# SCH_M5_GreenHat_Coil_Driver_2021-08-27.net
KiCad netlist of a schematic drawn in EasyEDA
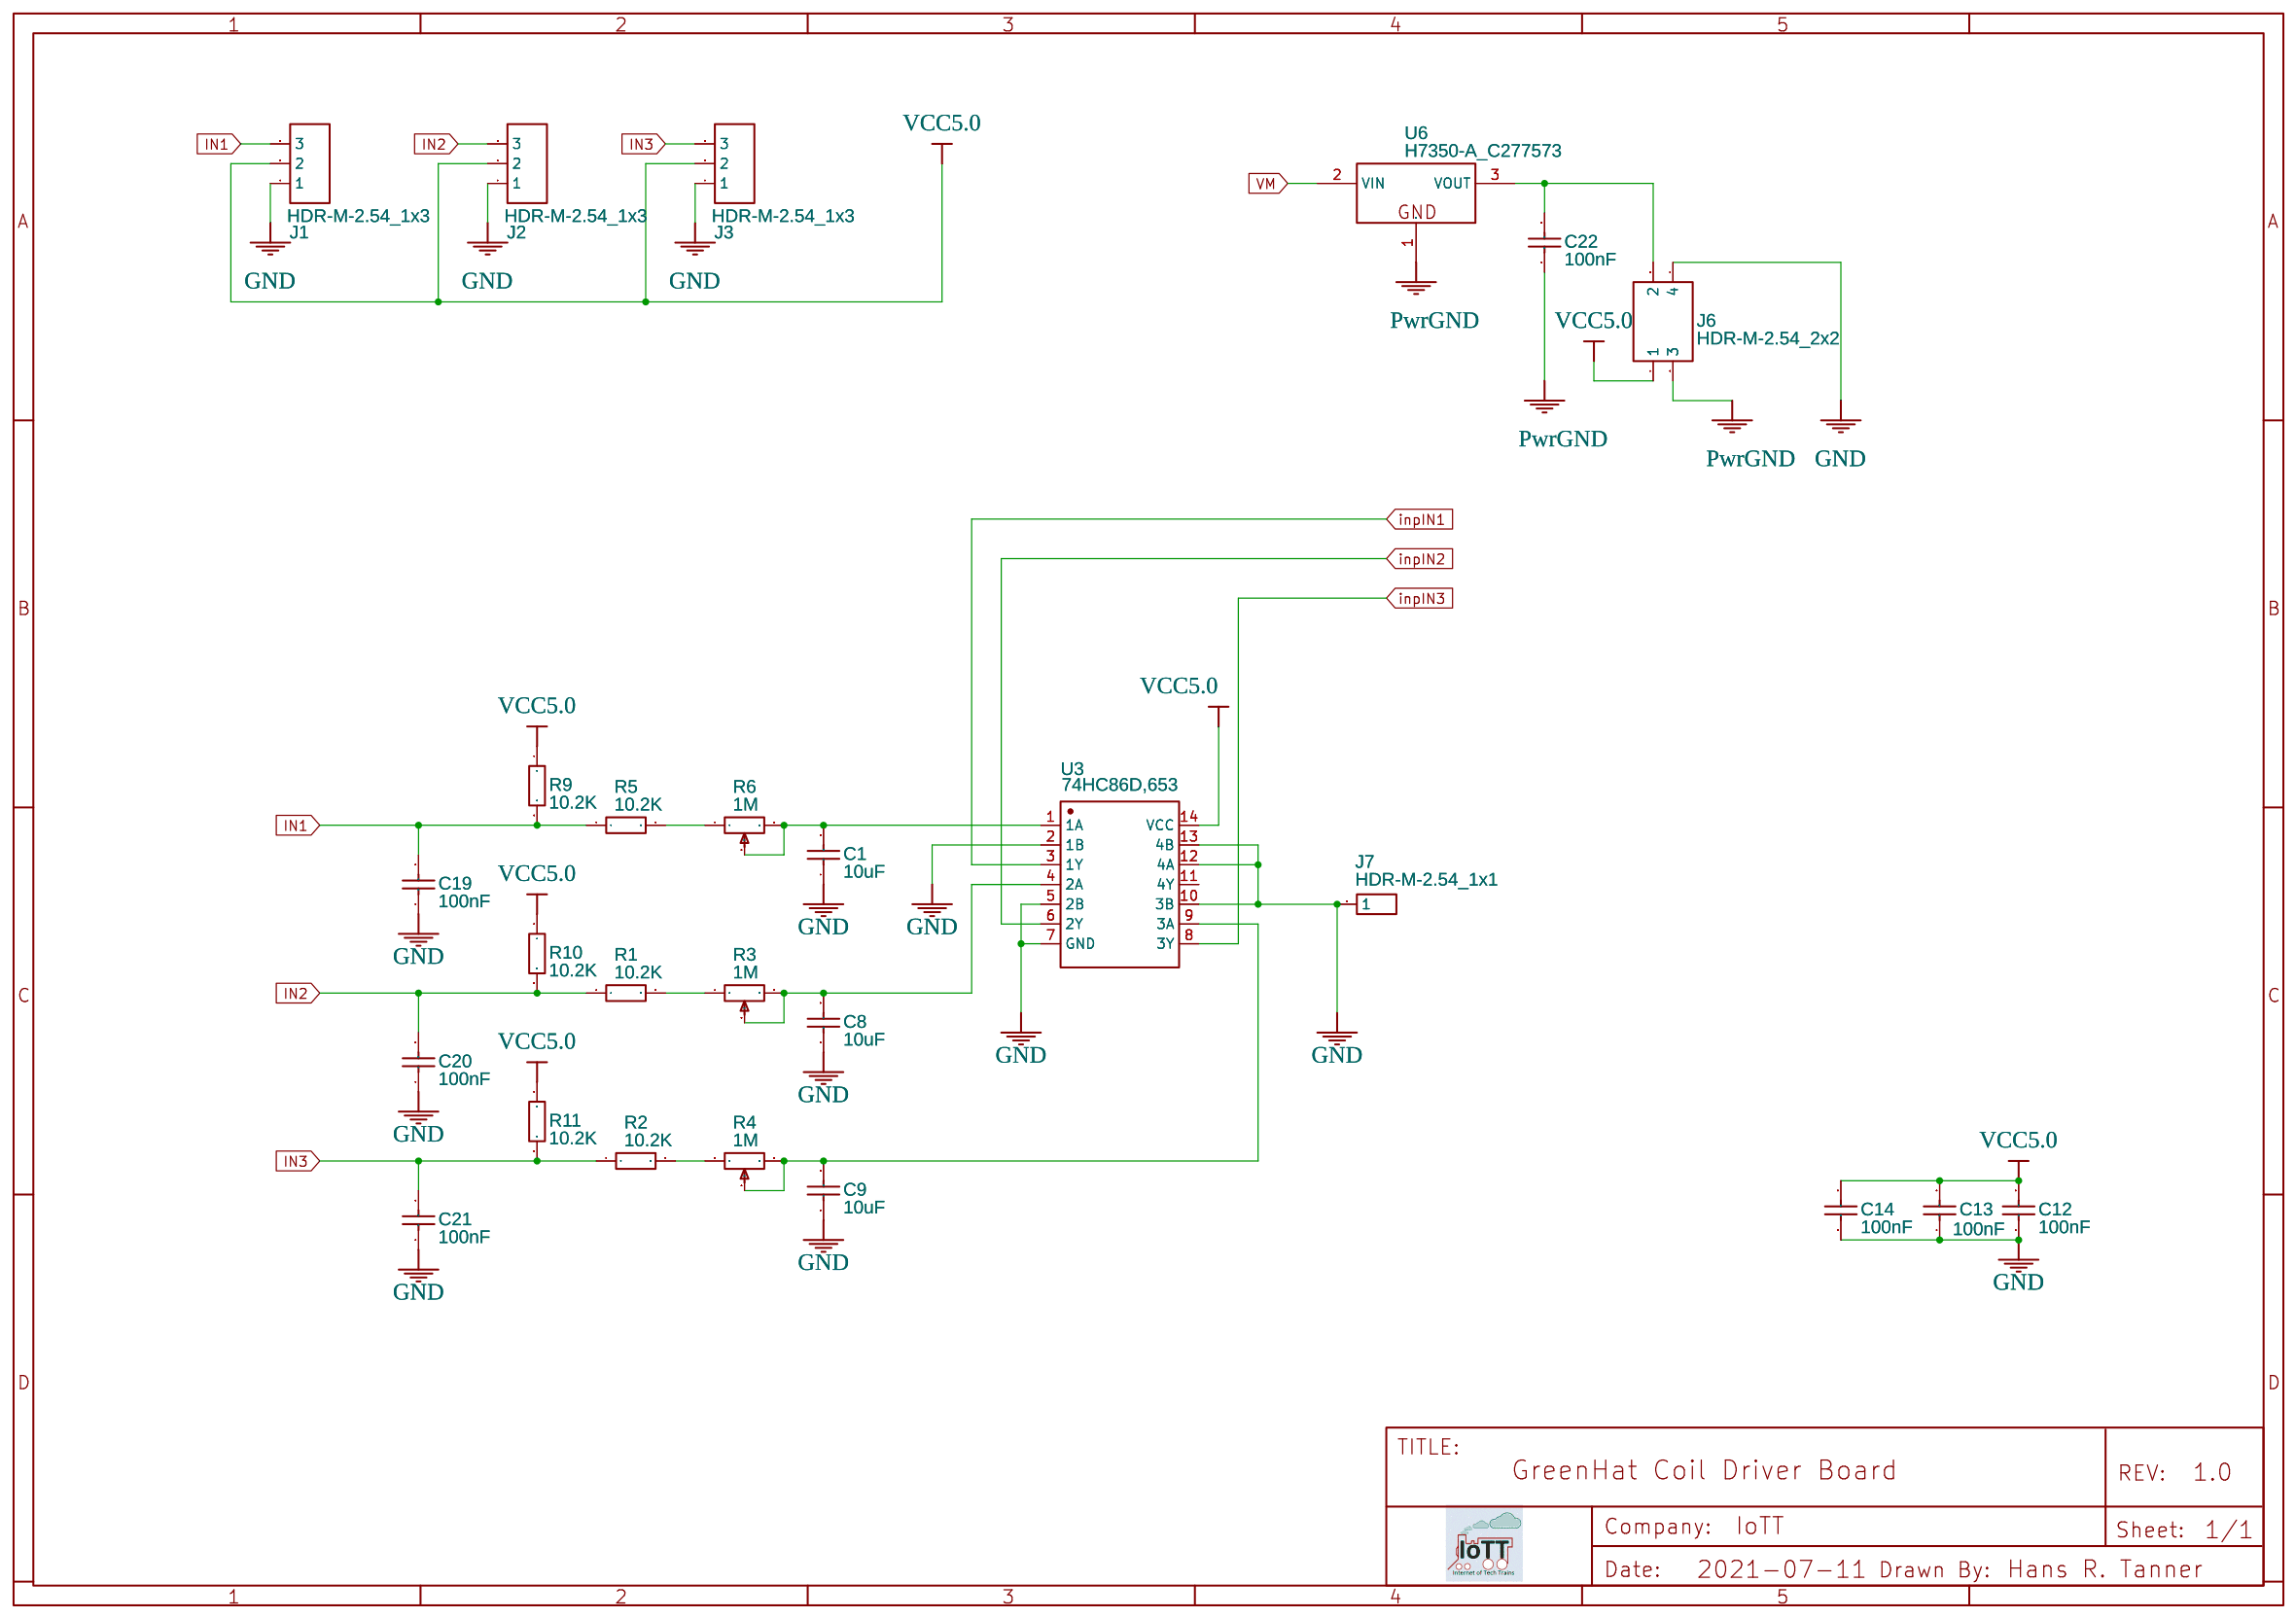
[diagram p0: Input Logic]
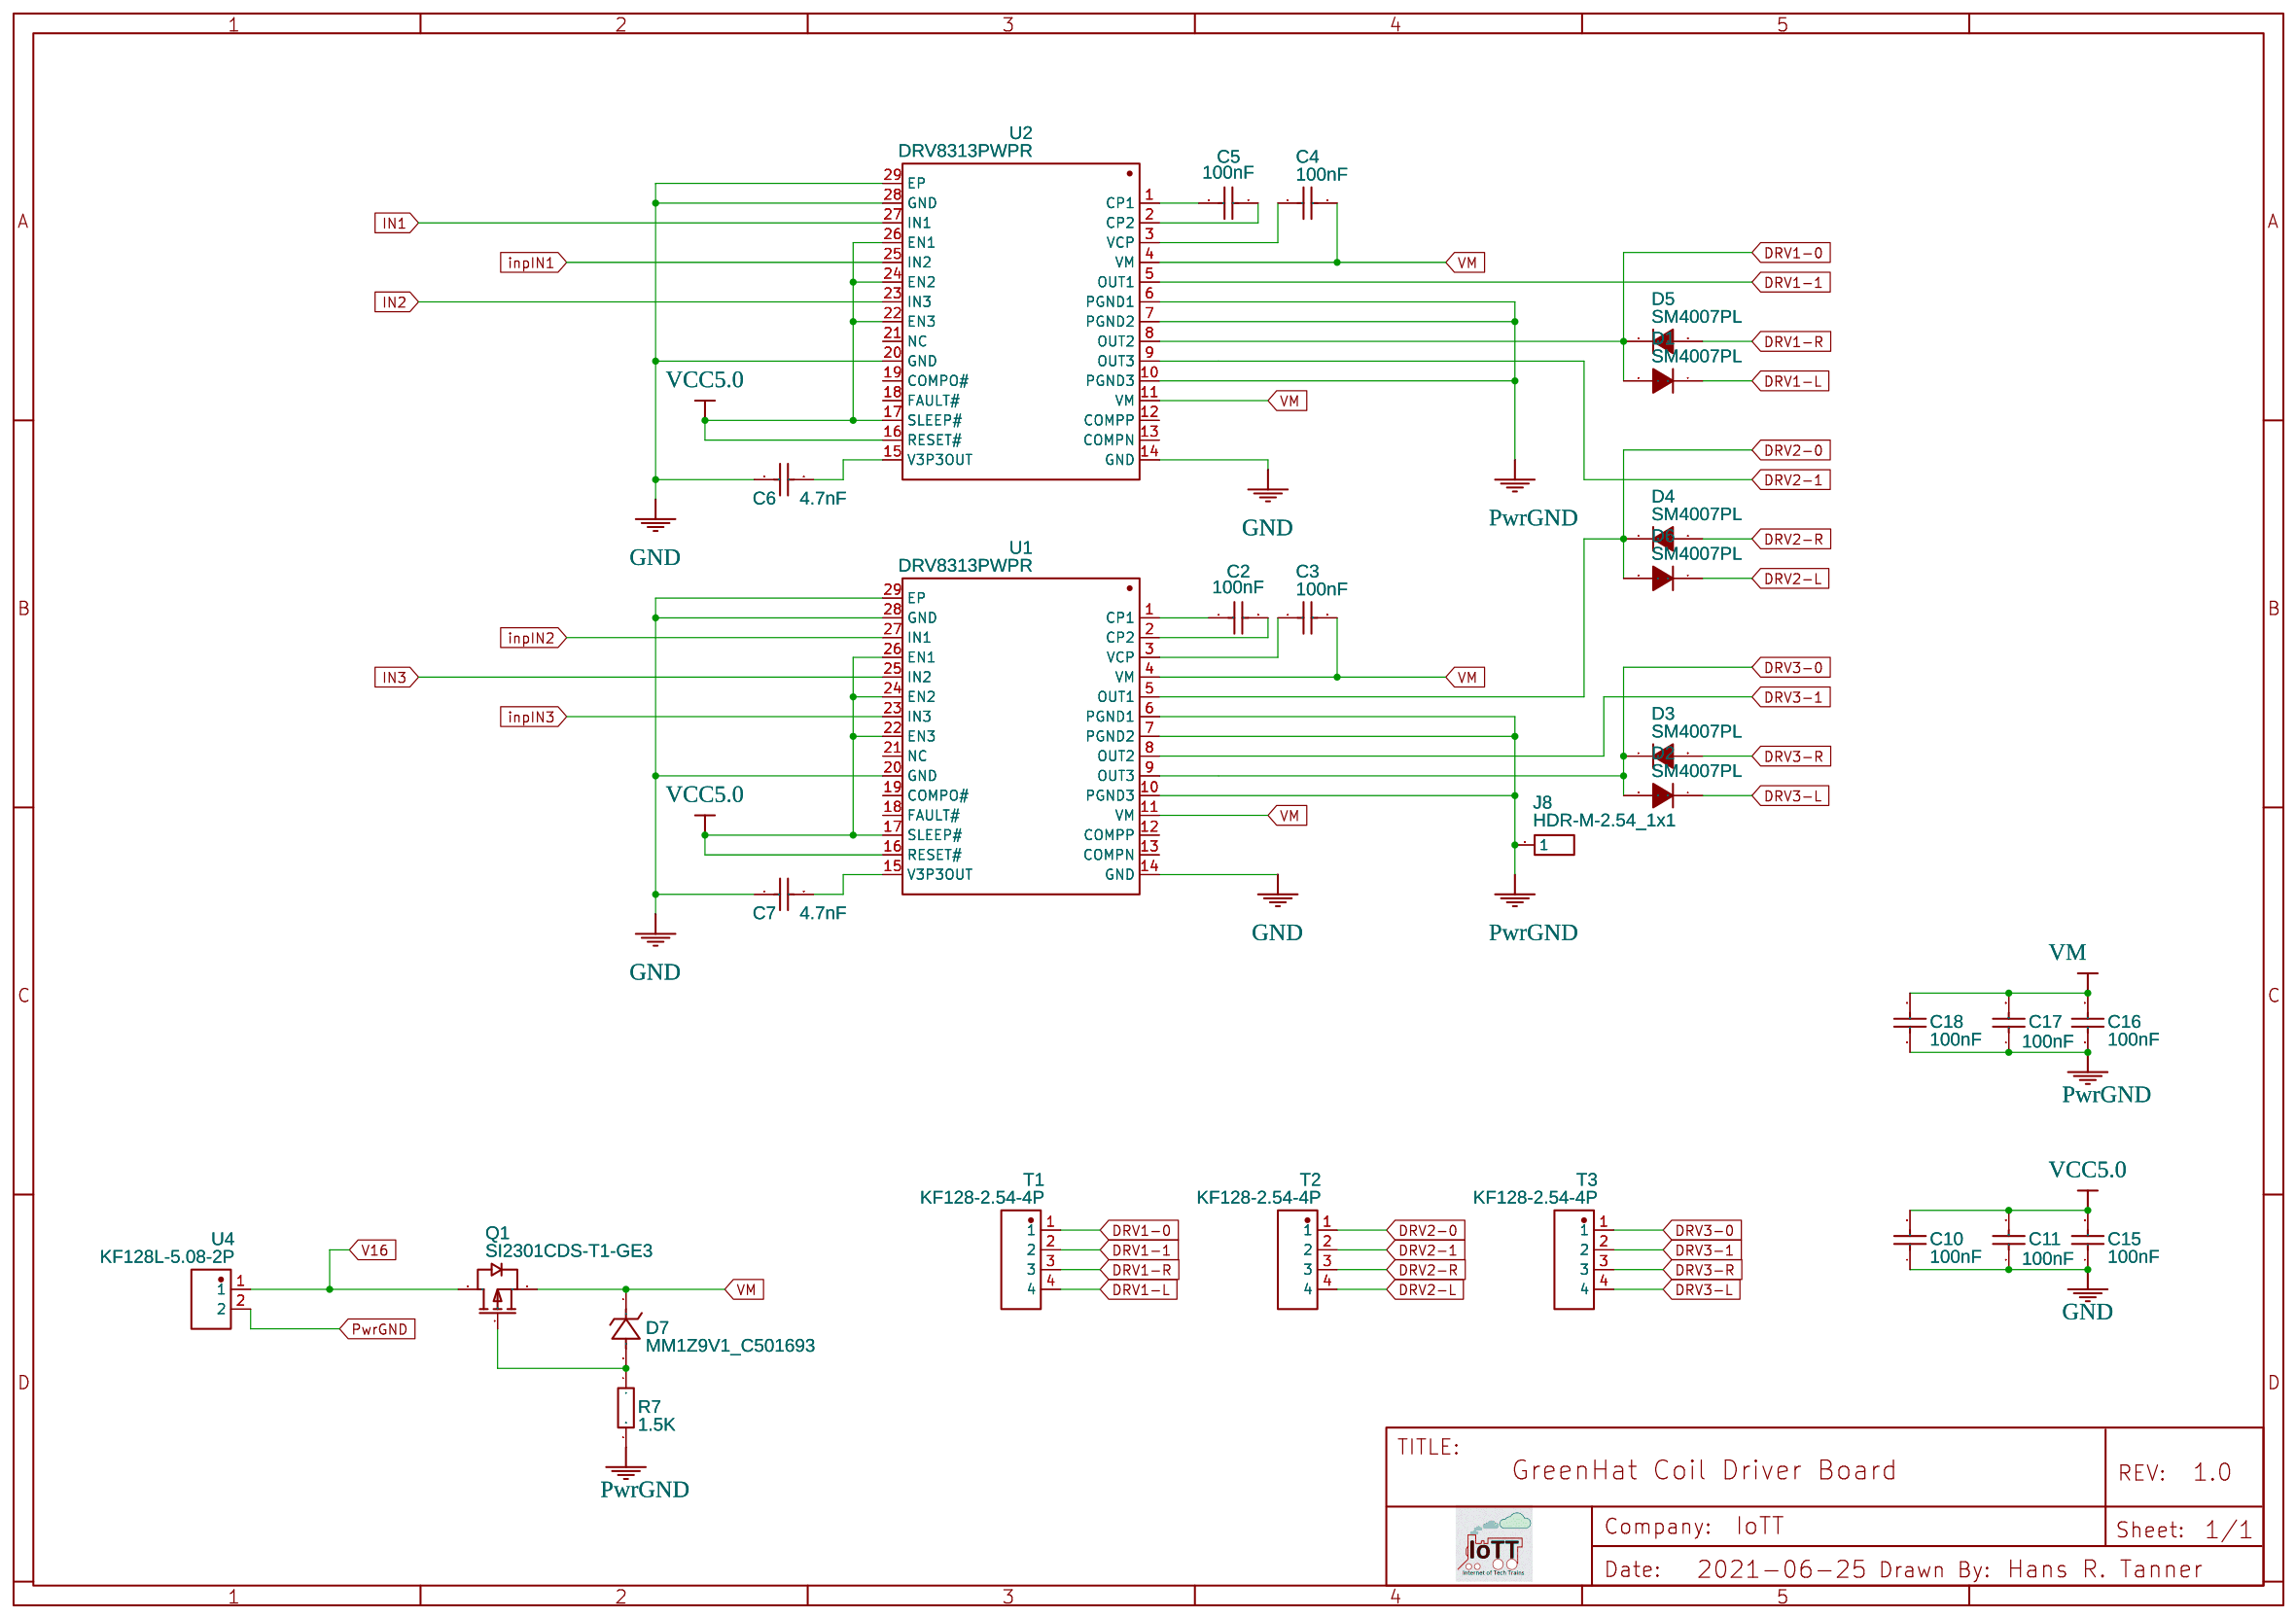
[diagram p1: Bridge]

(export (version "E")
  (design (tool "Eeschema 10.0.6"))
  (components
    (comp (ref "C1")
      (value "10uF")
      (fields
        (field (name "BOM_Manufacturer Part") "CL21A106KAYNNNE")
        (field (name "BOM_Supplier Part") "C15850")
      )
      (libsource (lib "") (part "CL21A106KAYNNNE"))
    )
    (comp (ref "C8")
      (value "10uF")
      (fields
        (field (name "BOM_Manufacturer Part") "CL21A106KAYNNNE")
        (field (name "BOM_Supplier Part") "C15850")
      )
      (libsource (lib "") (part "CL21A106KAYNNNE"))
    )
    (comp (ref "C9")
      (value "10uF")
      (fields
        (field (name "BOM_Manufacturer Part") "CL21A106KAYNNNE")
        (field (name "BOM_Supplier Part") "C15850")
      )
      (libsource (lib "") (part "CL21A106KAYNNNE"))
    )
    (comp (ref "C12")
      (value "100nF")
      (fields
        (field (name "BOM_Manufacturer Part") "CL05B104KO5NNNC")
        (field (name "BOM_Supplier Part") "C1525")
      )
      (libsource (lib "") (part "CL05B104KO5NNNC"))
    )
    (comp (ref "C13")
      (value "100nF")
      (fields
        (field (name "BOM_Manufacturer Part") "CL05B104KO5NNNC")
        (field (name "BOM_Supplier Part") "C1525")
      )
      (libsource (lib "") (part "CL05B104KO5NNNC"))
    )
    (comp (ref "C14")
      (value "100nF")
      (fields
        (field (name "BOM_Manufacturer Part") "CL05B104KO5NNNC")
        (field (name "BOM_Supplier Part") "C1525")
      )
      (libsource (lib "") (part "CL05B104KO5NNNC"))
    )
    (comp (ref "C19")
      (value "100nF")
      (fields
        (field (name "BOM_Manufacturer Part") "CL05B104KO5NNNC")
        (field (name "BOM_Supplier Part") "C1525")
      )
      (libsource (lib "") (part "CL05B104KO5NNNC"))
    )
    (comp (ref "C20")
      (value "100nF")
      (fields
        (field (name "BOM_Manufacturer Part") "CL05B104KO5NNNC")
        (field (name "BOM_Supplier Part") "C1525")
      )
      (libsource (lib "") (part "CL05B104KO5NNNC"))
    )
    (comp (ref "C21")
      (value "100nF")
      (fields
        (field (name "BOM_Manufacturer Part") "CL05B104KO5NNNC")
        (field (name "BOM_Supplier Part") "C1525")
      )
      (libsource (lib "") (part "CL05B104KO5NNNC"))
    )
    (comp (ref "C22")
      (value "100nF")
      (fields
        (field (name "BOM_Manufacturer Part") "CL05B104KO5NNNC")
        (field (name "BOM_Supplier Part") "C1525")
      )
      (libsource (lib "") (part "CL05B104KO5NNNC"))
    )
    (comp (ref "J1")
      (value "HDR-M-2.54_1x3")
      (fields (field (name "BOM_Supplier Part") "C180248"))
      (libsource (lib "") (part "HDR-M-2.54_1x3"))
    )
    (comp (ref "J2")
      (value "HDR-M-2.54_1x3")
      (fields (field (name "BOM_Supplier Part") "C180248"))
      (libsource (lib "") (part "HDR-M-2.54_1x3"))
    )
    (comp (ref "J3")
      (value "HDR-M-2.54_1x3")
      (fields (field (name "BOM_Supplier Part") "C180248"))
      (libsource (lib "") (part "HDR-M-2.54_1x3"))
    )
    (comp (ref "J6")
      (value "HDR-M-2.54_2x2")
      (fields (field (name "BOM_Supplier Part") "C66690"))
      (libsource (lib "") (part "HDR-M-2.54_2x2"))
    )
    (comp (ref "J7")
      (value "HDR-M-2.54_1x1")
      (fields (field (name "BOM_Supplier Part") "C81276"))
      (libsource (lib "") (part "HDR-M-2.54_1x1"))
    )
    (comp (ref "R1")
      (value "10.2K")
      (fields
        (field (name "BOM_Manufacturer Part") "RTT021022FTH")
        (field (name "BOM_Supplier Part") "C102756")
      )
      (libsource (lib "") (part "RTT021022FTH"))
    )
    (comp (ref "R2")
      (value "10.2K")
      (fields
        (field (name "BOM_Manufacturer Part") "RTT021022FTH")
        (field (name "BOM_Supplier Part") "C102756")
      )
      (libsource (lib "") (part "RTT021022FTH"))
    )
    (comp (ref "R3")
      (value "1M")
      (fields
        (field (name "BOM_Manufacturer Part") "3386P-1-105")
        (field (name "BOM_Supplier Part") "C118946")
      )
      (libsource (lib "") (part "3386P-1-105_C118946"))
    )
    (comp (ref "R4")
      (value "1M")
      (fields
        (field (name "BOM_Manufacturer Part") "3386P-1-105")
        (field (name "BOM_Supplier Part") "C118946")
      )
      (libsource (lib "") (part "3386P-1-105_C118946"))
    )
    (comp (ref "R5")
      (value "10.2K")
      (fields
        (field (name "BOM_Manufacturer Part") "RTT021022FTH")
        (field (name "BOM_Supplier Part") "C102756")
      )
      (libsource (lib "") (part "RTT021022FTH"))
    )
    (comp (ref "R6")
      (value "1M")
      (fields
        (field (name "BOM_Manufacturer Part") "3386P-1-105")
        (field (name "BOM_Supplier Part") "C118946")
      )
      (libsource (lib "") (part "3386P-1-105_C118946"))
    )
    (comp (ref "R9")
      (value "10.2K")
      (fields
        (field (name "BOM_Manufacturer Part") "RTT021022FTH")
        (field (name "BOM_Supplier Part") "C102756")
      )
      (libsource (lib "") (part "RTT021022FTH_1"))
    )
    (comp (ref "R10")
      (value "10.2K")
      (fields
        (field (name "BOM_Manufacturer Part") "RTT021022FTH")
        (field (name "BOM_Supplier Part") "C102756")
      )
      (libsource (lib "") (part "RTT021022FTH_1"))
    )
    (comp (ref "R11")
      (value "10.2K")
      (fields
        (field (name "BOM_Manufacturer Part") "RTT021022FTH")
        (field (name "BOM_Supplier Part") "C102756")
      )
      (libsource (lib "") (part "RTT021022FTH_1"))
    )
    (comp (ref "U3")
      (value "74HC86D,653")
      (fields (field (name "BOM_Supplier Part") "C5955"))
      (libsource (lib "") (part "74HC86D,653"))
    )
    (comp (ref "U6")
      (value "H7350-A_C277573")
      (fields (field (name "BOM_Manufacturer Part") "H7350-A") (field (name "BOM_Supplier Part") "C277573"))
      (libsource (lib "") (part "H7350-A_C277573"))
    )
    (comp (ref "C2")
      (value "100nF")
      (fields
        (field (name "BOM_Manufacturer Part") "CL05B104KO5NNNC")
        (field (name "BOM_Supplier Part") "C1525")
      )
      (libsource (lib "") (part "CL05B104KO5NNNC_1"))
    )
    (comp (ref "C3")
      (value "100nF")
      (fields
        (field (name "BOM_Manufacturer Part") "CL05B104KO5NNNC")
        (field (name "BOM_Supplier Part") "C1525")
      )
      (libsource (lib "") (part "CL05B104KO5NNNC_1"))
    )
    (comp (ref "C4")
      (value "100nF")
      (fields
        (field (name "BOM_Manufacturer Part") "CL05B104KO5NNNC")
        (field (name "BOM_Supplier Part") "C1525")
      )
      (libsource (lib "") (part "CL05B104KO5NNNC_1"))
    )
    (comp (ref "C5")
      (value "100nF")
      (fields
        (field (name "BOM_Manufacturer Part") "CL05B104KO5NNNC")
        (field (name "BOM_Supplier Part") "C1525")
      )
      (libsource (lib "") (part "CL05B104KO5NNNC_1"))
    )
    (comp (ref "C6")
      (value "4.7nF")
      (fields
        (field (name "BOM_Manufacturer Part") "0402B472K500NT")
        (field (name "BOM_Supplier Part") "C1538")
      )
      (libsource (lib "") (part "0402B472K500NT"))
    )
    (comp (ref "C7")
      (value "4.7nF")
      (fields
        (field (name "BOM_Manufacturer Part") "0402B472K500NT")
        (field (name "BOM_Supplier Part") "C1538")
      )
      (libsource (lib "") (part "0402B472K500NT"))
    )
    (comp (ref "C10")
      (value "100nF")
      (fields
        (field (name "BOM_Manufacturer Part") "CL05B104KO5NNNC")
        (field (name "BOM_Supplier Part") "C1525")
      )
      (libsource (lib "") (part "CL05B104KO5NNNC"))
    )
    (comp (ref "C11")
      (value "100nF")
      (fields
        (field (name "BOM_Manufacturer Part") "CL05B104KO5NNNC")
        (field (name "BOM_Supplier Part") "C1525")
      )
      (libsource (lib "") (part "CL05B104KO5NNNC"))
    )
    (comp (ref "C15")
      (value "100nF")
      (fields
        (field (name "BOM_Manufacturer Part") "CL05B104KO5NNNC")
        (field (name "BOM_Supplier Part") "C1525")
      )
      (libsource (lib "") (part "CL05B104KO5NNNC"))
    )
    (comp (ref "C16")
      (value "100nF")
      (fields
        (field (name "BOM_Manufacturer Part") "CL05B104KO5NNNC")
        (field (name "BOM_Supplier Part") "C1525")
      )
      (libsource (lib "") (part "CL05B104KO5NNNC"))
    )
    (comp (ref "C17")
      (value "100nF")
      (fields
        (field (name "BOM_Manufacturer Part") "CL05B104KO5NNNC")
        (field (name "BOM_Supplier Part") "C1525")
      )
      (libsource (lib "") (part "CL05B104KO5NNNC"))
    )
    (comp (ref "C18")
      (value "100nF")
      (fields
        (field (name "BOM_Manufacturer Part") "CL05B104KO5NNNC")
        (field (name "BOM_Supplier Part") "C1525")
      )
      (libsource (lib "") (part "CL05B104KO5NNNC"))
    )
    (comp (ref "D1")
      (value "SM4007PL")
      (fields (field (name "BOM_Supplier Part") "C64898"))
      (libsource (lib "") (part "SM4007PL"))
    )
    (comp (ref "D2")
      (value "SM4007PL")
      (fields (field (name "BOM_Supplier Part") "C64898"))
      (libsource (lib "") (part "SM4007PL"))
    )
    (comp (ref "D3")
      (value "SM4007PL")
      (fields (field (name "BOM_Supplier Part") "C64898"))
      (libsource (lib "") (part "SM4007PL_1"))
    )
    (comp (ref "D4")
      (value "SM4007PL")
      (fields (field (name "BOM_Supplier Part") "C64898"))
      (libsource (lib "") (part "SM4007PL_1"))
    )
    (comp (ref "D5")
      (value "SM4007PL")
      (fields (field (name "BOM_Supplier Part") "C64898"))
      (libsource (lib "") (part "SM4007PL_1"))
    )
    (comp (ref "D6")
      (value "SM4007PL")
      (fields (field (name "BOM_Supplier Part") "C64898"))
      (libsource (lib "") (part "SM4007PL"))
    )
    (comp (ref "D7")
      (value "MM1Z9V1_C501693")
      (fields (field (name "BOM_Manufacturer Part") "MM1Z9V1") (field (name "BOM_Supplier Part") "C501693"))
      (libsource (lib "") (part "MM1Z9V1_C501693"))
    )
    (comp (ref "J8")
      (value "HDR-M-2.54_1x1")
      (fields (field (name "BOM_Supplier Part") "C81276"))
      (libsource (lib "") (part "HDR-M-2.54_1x1"))
    )
    (comp (ref "Q1")
      (value "SI2301CDS-T1-GE3")
      (fields (field (name "BOM_Supplier Part") "C10487"))
      (libsource (lib "") (part "SI2301CDS-T1-GE3"))
    )
    (comp (ref "R7")
      (value "1.5K")
      (fields
        (field (name "BOM_Manufacturer Part") "0402WGF1501TCE")
        (field (name "BOM_Supplier Part") "C25867")
      )
      (libsource (lib "") (part "0402WGF1501TCE"))
    )
    (comp (ref "T1")
      (value "KF128-2.54-4P")
      (fields (field (name "BOM_Supplier Part") "C474922"))
      (libsource (lib "") (part "KF128-2.54-4P"))
    )
    (comp (ref "T2")
      (value "KF128-2.54-4P")
      (fields (field (name "BOM_Supplier Part") "C474922"))
      (libsource (lib "") (part "KF128-2.54-4P"))
    )
    (comp (ref "T3")
      (value "KF128-2.54-4P")
      (fields (field (name "BOM_Supplier Part") "C474922"))
      (libsource (lib "") (part "KF128-2.54-4P"))
    )
    (comp (ref "U1")
      (value "DRV8313PWPR")
      (fields (field (name "BOM_Supplier Part") "C92482"))
      (libsource (lib "") (part "DRV8313PWPR"))
    )
    (comp (ref "U2")
      (value "DRV8313PWPR")
      (fields (field (name "BOM_Supplier Part") "C92482"))
      (libsource (lib "") (part "DRV8313PWPR"))
    )
    (comp (ref "U4")
      (value "KF128L-5.08-2P")
      (fields (field (name "BOM_Supplier Part") "C474940"))
      (libsource (lib "") (part "KF128L-5.08-2P"))
    )
  )
  (nets
    (net (code "1") (name "DRV1-0") (class "Default")
      (node (ref "D1") (pin "2") (pinfunction "A_2") (pintype "unspecified"))
      (node (ref "D5") (pin "1") (pinfunction "C_1") (pintype "unspecified"))
      (node (ref "T1") (pin "1") (pinfunction "1_1") (pintype "unspecified"))
      (node (ref "U2") (pin "8") (pinfunction "OUT2_8") (pintype "unspecified"))
    )
    (net (code "2") (name "DRV1-1") (class "Default")
      (node (ref "T1") (pin "2") (pinfunction "2_2") (pintype "unspecified"))
      (node (ref "U2") (pin "5") (pinfunction "OUT1_5") (pintype "unspecified"))
    )
    (net (code "3") (name "DRV1-L") (class "Default")
      (node (ref "D1") (pin "1") (pinfunction "C_1") (pintype "unspecified"))
      (node (ref "T1") (pin "4") (pinfunction "4_4") (pintype "unspecified"))
    )
    (net (code "4") (name "DRV1-R") (class "Default")
      (node (ref "D5") (pin "2") (pinfunction "A_2") (pintype "unspecified"))
      (node (ref "T1") (pin "3") (pinfunction "3_3") (pintype "unspecified"))
    )
    (net (code "5") (name "DRV2-0") (class "Default")
      (node (ref "D4") (pin "1") (pinfunction "C_1") (pintype "unspecified"))
      (node (ref "D6") (pin "2") (pinfunction "A_2") (pintype "unspecified"))
      (node (ref "T2") (pin "1") (pinfunction "1_1") (pintype "unspecified"))
      (node (ref "U1") (pin "5") (pinfunction "OUT1_5") (pintype "unspecified"))
    )
    (net (code "6") (name "DRV2-1") (class "Default")
      (node (ref "T2") (pin "2") (pinfunction "2_2") (pintype "unspecified"))
      (node (ref "U2") (pin "9") (pinfunction "OUT3_9") (pintype "unspecified"))
    )
    (net (code "7") (name "DRV2-L") (class "Default")
      (node (ref "D6") (pin "1") (pinfunction "C_1") (pintype "unspecified"))
      (node (ref "T2") (pin "4") (pinfunction "4_4") (pintype "unspecified"))
    )
    (net (code "8") (name "DRV2-R") (class "Default")
      (node (ref "D4") (pin "2") (pinfunction "A_2") (pintype "unspecified"))
      (node (ref "T2") (pin "3") (pinfunction "3_3") (pintype "unspecified"))
    )
    (net (code "9") (name "DRV3-0") (class "Default")
      (node (ref "D2") (pin "2") (pinfunction "A_2") (pintype "unspecified"))
      (node (ref "D3") (pin "1") (pinfunction "C_1") (pintype "unspecified"))
      (node (ref "T3") (pin "1") (pinfunction "1_1") (pintype "unspecified"))
      (node (ref "U1") (pin "9") (pinfunction "OUT3_9") (pintype "unspecified"))
    )
    (net (code "10") (name "DRV3-1") (class "Default")
      (node (ref "T3") (pin "2") (pinfunction "2_2") (pintype "unspecified"))
      (node (ref "U1") (pin "8") (pinfunction "OUT2_8") (pintype "unspecified"))
    )
    (net (code "11") (name "DRV3-L") (class "Default")
      (node (ref "D2") (pin "1") (pinfunction "C_1") (pintype "unspecified"))
      (node (ref "T3") (pin "4") (pinfunction "4_4") (pintype "unspecified"))
    )
    (net (code "12") (name "DRV3-R") (class "Default")
      (node (ref "D3") (pin "2") (pinfunction "A_2") (pintype "unspecified"))
      (node (ref "T3") (pin "3") (pinfunction "3_3") (pintype "unspecified"))
    )
    (net (code "13") (name "GND") (class "Default")
      (node (ref "C1") (pin "1") (pinfunction "1_1") (pintype "input"))
      (node (ref "C10") (pin "1") (pinfunction "1_1") (pintype "input"))
      (node (ref "C11") (pin "1") (pinfunction "1_1") (pintype "input"))
      (node (ref "C12") (pin "1") (pinfunction "1_1") (pintype "input"))
      (node (ref "C13") (pin "1") (pinfunction "1_1") (pintype "input"))
      (node (ref "C14") (pin "1") (pinfunction "1_1") (pintype "input"))
      (node (ref "C15") (pin "1") (pinfunction "1_1") (pintype "input"))
      (node (ref "C19") (pin "1") (pinfunction "1_1") (pintype "input"))
      (node (ref "C20") (pin "1") (pinfunction "1_1") (pintype "input"))
      (node (ref "C21") (pin "1") (pinfunction "1_1") (pintype "input"))
      (node (ref "C6") (pin "1") (pinfunction "1_1") (pintype "input"))
      (node (ref "C7") (pin "1") (pinfunction "1_1") (pintype "input"))
      (node (ref "C8") (pin "1") (pinfunction "1_1") (pintype "input"))
      (node (ref "C9") (pin "1") (pinfunction "1_1") (pintype "input"))
      (node (ref "J1") (pin "1") (pinfunction "1_1") (pintype "input"))
      (node (ref "J2") (pin "1") (pinfunction "1_1") (pintype "input"))
      (node (ref "J3") (pin "1") (pinfunction "1_1") (pintype "input"))
      (node (ref "J6") (pin "4") (pinfunction "4_4") (pintype "input"))
      (node (ref "J7") (pin "1") (pinfunction "1_1") (pintype "input"))
      (node (ref "U1") (pin "14") (pinfunction "GND_14") (pintype "unspecified"))
      (node (ref "U1") (pin "20") (pinfunction "GND_20") (pintype "unspecified"))
      (node (ref "U1") (pin "28") (pinfunction "GND_28") (pintype "unspecified"))
      (node (ref "U1") (pin "29") (pinfunction "EP_29") (pintype "unspecified"))
      (node (ref "U2") (pin "14") (pinfunction "GND_14") (pintype "unspecified"))
      (node (ref "U2") (pin "20") (pinfunction "GND_20") (pintype "unspecified"))
      (node (ref "U2") (pin "28") (pinfunction "GND_28") (pintype "unspecified"))
      (node (ref "U2") (pin "29") (pinfunction "EP_29") (pintype "unspecified"))
      (node (ref "U3") (pin "10") (pinfunction "3B_10") (pintype "unspecified"))
      (node (ref "U3") (pin "12") (pinfunction "4A_12") (pintype "unspecified"))
      (node (ref "U3") (pin "13") (pinfunction "4B_13") (pintype "unspecified"))
      (node (ref "U3") (pin "2") (pinfunction "1B_2") (pintype "unspecified"))
      (node (ref "U3") (pin "5") (pinfunction "2B_5") (pintype "unspecified"))
      (node (ref "U3") (pin "7") (pinfunction "GND_7") (pintype "unspecified"))
    )
    (net (code "14") (name "IN1") (class "Default")
      (node (ref "C19") (pin "2") (pinfunction "2_2") (pintype "input"))
      (node (ref "J1") (pin "3") (pinfunction "3_3") (pintype "input"))
      (node (ref "R5") (pin "1") (pinfunction "1_1") (pintype "input"))
      (node (ref "R9") (pin "2") (pinfunction "2_2") (pintype "input"))
      (node (ref "U2") (pin "27") (pinfunction "IN1_27") (pintype "unspecified"))
    )
    (net (code "15") (name "IN2") (class "Default")
      (node (ref "C20") (pin "2") (pinfunction "2_2") (pintype "input"))
      (node (ref "J2") (pin "3") (pinfunction "3_3") (pintype "input"))
      (node (ref "R1") (pin "1") (pinfunction "1_1") (pintype "input"))
      (node (ref "R10") (pin "2") (pinfunction "2_2") (pintype "input"))
      (node (ref "U2") (pin "23") (pinfunction "IN3_23") (pintype "unspecified"))
    )
    (net (code "16") (name "IN3") (class "Default")
      (node (ref "C21") (pin "2") (pinfunction "2_2") (pintype "input"))
      (node (ref "J3") (pin "3") (pinfunction "3_3") (pintype "input"))
      (node (ref "R11") (pin "2") (pinfunction "2_2") (pintype "input"))
      (node (ref "R2") (pin "1") (pinfunction "1_1") (pintype "input"))
      (node (ref "U1") (pin "25") (pinfunction "IN2_25") (pintype "unspecified"))
    )
    (net (code "17") (name "Net-(D7-A)") (class "Default")
      (node (ref "D7") (pin "2") (pinfunction "A_2") (pintype "unspecified"))
      (node (ref "Q1") (pin "1") (pinfunction "G_1") (pintype "unspecified"))
      (node (ref "R7") (pin "1") (pinfunction "1_1") (pintype "input"))
    )
    (net (code "18") (name "Net-(R1-Pad2)") (class "Default")
      (node (ref "R1") (pin "2") (pinfunction "2_2") (pintype "input"))
      (node (ref "R3") (pin "1") (pinfunction "1_1") (pintype "input"))
    )
    (net (code "19") (name "Net-(R2-Pad2)") (class "Default")
      (node (ref "R2") (pin "2") (pinfunction "2_2") (pintype "input"))
      (node (ref "R4") (pin "1") (pinfunction "1_1") (pintype "input"))
    )
    (net (code "20") (name "Net-(R5-Pad2)") (class "Default")
      (node (ref "R5") (pin "2") (pinfunction "2_2") (pintype "input"))
      (node (ref "R6") (pin "1") (pinfunction "1_1") (pintype "input"))
    )
    (net (code "21") (name "Net-(U1-CP1)") (class "Default")
      (node (ref "C2") (pin "1") (pinfunction "1_1") (pintype "input"))
      (node (ref "U1") (pin "1") (pinfunction "CP1_1") (pintype "unspecified"))
    )
    (net (code "22") (name "Net-(U1-CP2)") (class "Default")
      (node (ref "C2") (pin "2") (pinfunction "2_2") (pintype "input"))
      (node (ref "U1") (pin "2") (pinfunction "CP2_2") (pintype "unspecified"))
    )
    (net (code "23") (name "Net-(U1-V3P3OUT)") (class "Default")
      (node (ref "C7") (pin "2") (pinfunction "2_2") (pintype "input"))
      (node (ref "U1") (pin "15") (pinfunction "V3P3OUT_15") (pintype "unspecified"))
    )
    (net (code "24") (name "Net-(U1-VCP)") (class "Default")
      (node (ref "C3") (pin "1") (pinfunction "1_1") (pintype "input"))
      (node (ref "U1") (pin "3") (pinfunction "VCP_3") (pintype "unspecified"))
    )
    (net (code "25") (name "Net-(U2-CP1)") (class "Default")
      (node (ref "C5") (pin "1") (pinfunction "1_1") (pintype "input"))
      (node (ref "U2") (pin "1") (pinfunction "CP1_1") (pintype "unspecified"))
    )
    (net (code "26") (name "Net-(U2-CP2)") (class "Default")
      (node (ref "C5") (pin "2") (pinfunction "2_2") (pintype "input"))
      (node (ref "U2") (pin "2") (pinfunction "CP2_2") (pintype "unspecified"))
    )
    (net (code "27") (name "Net-(U2-V3P3OUT)") (class "Default")
      (node (ref "C6") (pin "2") (pinfunction "2_2") (pintype "input"))
      (node (ref "U2") (pin "15") (pinfunction "V3P3OUT_15") (pintype "unspecified"))
    )
    (net (code "28") (name "Net-(U2-VCP)") (class "Default")
      (node (ref "C4") (pin "1") (pinfunction "1_1") (pintype "input"))
      (node (ref "U2") (pin "3") (pinfunction "VCP_3") (pintype "unspecified"))
    )
    (net (code "29") (name "Net-(U3-1A)") (class "Default")
      (node (ref "C1") (pin "2") (pinfunction "2_2") (pintype "input"))
      (node (ref "R6") (pin "2") (pinfunction "2_2") (pintype "input"))
      (node (ref "R6") (pin "3") (pinfunction "3_3") (pintype "input"))
      (node (ref "U3") (pin "1") (pinfunction "1A_1") (pintype "unspecified"))
    )
    (net (code "30") (name "Net-(U3-2A)") (class "Default")
      (node (ref "C8") (pin "2") (pinfunction "2_2") (pintype "input"))
      (node (ref "R3") (pin "2") (pinfunction "2_2") (pintype "input"))
      (node (ref "R3") (pin "3") (pinfunction "3_3") (pintype "input"))
      (node (ref "U3") (pin "4") (pinfunction "2A_4") (pintype "unspecified"))
    )
    (net (code "31") (name "Net-(U3-3A)") (class "Default")
      (node (ref "C9") (pin "2") (pinfunction "2_2") (pintype "input"))
      (node (ref "R4") (pin "2") (pinfunction "2_2") (pintype "input"))
      (node (ref "R4") (pin "3") (pinfunction "3_3") (pintype "input"))
      (node (ref "U3") (pin "9") (pinfunction "3A_9") (pintype "unspecified"))
    )
    (net (code "32") (name "Net-(U6-VOUT)") (class "Default")
      (node (ref "C22") (pin "2") (pinfunction "2_2") (pintype "input"))
      (node (ref "J6") (pin "2") (pinfunction "2_2") (pintype "input"))
      (node (ref "U6") (pin "3") (pinfunction "VOUT_3") (pintype "passive"))
    )
    (net (code "33") (name "PwrGND") (class "Default")
      (node (ref "C16") (pin "1") (pinfunction "1_1") (pintype "input"))
      (node (ref "C17") (pin "1") (pinfunction "1_1") (pintype "input"))
      (node (ref "C18") (pin "1") (pinfunction "1_1") (pintype "input"))
      (node (ref "C22") (pin "1") (pinfunction "1_1") (pintype "input"))
      (node (ref "J6") (pin "3") (pinfunction "3_3") (pintype "input"))
      (node (ref "J8") (pin "1") (pinfunction "1_1") (pintype "input"))
      (node (ref "R7") (pin "2") (pinfunction "2_2") (pintype "input"))
      (node (ref "U1") (pin "10") (pinfunction "PGND3_10") (pintype "unspecified"))
      (node (ref "U1") (pin "6") (pinfunction "PGND1_6") (pintype "unspecified"))
      (node (ref "U1") (pin "7") (pinfunction "PGND2_7") (pintype "unspecified"))
      (node (ref "U2") (pin "10") (pinfunction "PGND3_10") (pintype "unspecified"))
      (node (ref "U2") (pin "6") (pinfunction "PGND1_6") (pintype "unspecified"))
      (node (ref "U2") (pin "7") (pinfunction "PGND2_7") (pintype "unspecified"))
      (node (ref "U4") (pin "2") (pinfunction "2_2") (pintype "unspecified"))
      (node (ref "U6") (pin "1") (pinfunction "GND_1") (pintype "unspecified"))
    )
    (net (code "34") (name "V16") (class "Default")
      (node (ref "Q1") (pin "3") (pinfunction "D_3") (pintype "unspecified"))
      (node (ref "U4") (pin "1") (pinfunction "1_1") (pintype "unspecified"))
    )
    (net (code "35") (name "VCC5.0") (class "Default")
      (node (ref "C10") (pin "2") (pinfunction "2_2") (pintype "input"))
      (node (ref "C11") (pin "2") (pinfunction "2_2") (pintype "input"))
      (node (ref "C12") (pin "2") (pinfunction "2_2") (pintype "input"))
      (node (ref "C13") (pin "2") (pinfunction "2_2") (pintype "input"))
      (node (ref "C14") (pin "2") (pinfunction "2_2") (pintype "input"))
      (node (ref "C15") (pin "2") (pinfunction "2_2") (pintype "input"))
      (node (ref "J1") (pin "2") (pinfunction "2_2") (pintype "input"))
      (node (ref "J2") (pin "2") (pinfunction "2_2") (pintype "input"))
      (node (ref "J3") (pin "2") (pinfunction "2_2") (pintype "input"))
      (node (ref "J6") (pin "1") (pinfunction "1_1") (pintype "input"))
      (node (ref "R10") (pin "1") (pinfunction "1_1") (pintype "input"))
      (node (ref "R11") (pin "1") (pinfunction "1_1") (pintype "input"))
      (node (ref "R9") (pin "1") (pinfunction "1_1") (pintype "input"))
      (node (ref "U1") (pin "16") (pinfunction "RESET#_16") (pintype "unspecified"))
      (node (ref "U1") (pin "17") (pinfunction "SLEEP#_17") (pintype "unspecified"))
      (node (ref "U1") (pin "22") (pinfunction "EN3_22") (pintype "unspecified"))
      (node (ref "U1") (pin "24") (pinfunction "EN2_24") (pintype "unspecified"))
      (node (ref "U1") (pin "26") (pinfunction "EN1_26") (pintype "unspecified"))
      (node (ref "U2") (pin "16") (pinfunction "RESET#_16") (pintype "unspecified"))
      (node (ref "U2") (pin "17") (pinfunction "SLEEP#_17") (pintype "unspecified"))
      (node (ref "U2") (pin "22") (pinfunction "EN3_22") (pintype "unspecified"))
      (node (ref "U2") (pin "24") (pinfunction "EN2_24") (pintype "unspecified"))
      (node (ref "U2") (pin "26") (pinfunction "EN1_26") (pintype "unspecified"))
      (node (ref "U3") (pin "14") (pinfunction "VCC_14") (pintype "unspecified"))
    )
    (net (code "36") (name "VM") (class "Default")
      (node (ref "C16") (pin "2") (pinfunction "2_2") (pintype "input"))
      (node (ref "C17") (pin "2") (pinfunction "2_2") (pintype "input"))
      (node (ref "C18") (pin "2") (pinfunction "2_2") (pintype "input"))
      (node (ref "C3") (pin "2") (pinfunction "2_2") (pintype "input"))
      (node (ref "C4") (pin "2") (pinfunction "2_2") (pintype "input"))
      (node (ref "D7") (pin "1") (pinfunction "K_1") (pintype "unspecified"))
      (node (ref "Q1") (pin "2") (pinfunction "S_2") (pintype "unspecified"))
      (node (ref "U1") (pin "11") (pinfunction "VM_11") (pintype "unspecified"))
      (node (ref "U1") (pin "4") (pinfunction "VM_4") (pintype "unspecified"))
      (node (ref "U2") (pin "11") (pinfunction "VM_11") (pintype "unspecified"))
      (node (ref "U2") (pin "4") (pinfunction "VM_4") (pintype "unspecified"))
      (node (ref "U6") (pin "2") (pinfunction "VIN_2") (pintype "unspecified"))
    )
    (net (code "37") (name "inpIN1") (class "Default")
      (node (ref "U2") (pin "25") (pinfunction "IN2_25") (pintype "unspecified"))
      (node (ref "U3") (pin "3") (pinfunction "1Y_3") (pintype "unspecified"))
    )
    (net (code "38") (name "inpIN2") (class "Default")
      (node (ref "U1") (pin "27") (pinfunction "IN1_27") (pintype "unspecified"))
      (node (ref "U3") (pin "6") (pinfunction "2Y_6") (pintype "unspecified"))
    )
    (net (code "39") (name "inpIN3") (class "Default")
      (node (ref "U1") (pin "23") (pinfunction "IN3_23") (pintype "unspecified"))
      (node (ref "U3") (pin "8") (pinfunction "3Y_8") (pintype "unspecified"))
    )
    (net (code "40") (name "unconnected-(U1-COMPN-Pad13)") (class "Default")
      (node (ref "U1") (pin "13") (pinfunction "COMPN_13") (pintype "unspecified"))
    )
    (net (code "41") (name "unconnected-(U1-COMPO#-Pad19)") (class "Default")
      (node (ref "U1") (pin "19") (pinfunction "COMPO#_19") (pintype "unspecified"))
    )
    (net (code "42") (name "unconnected-(U1-COMPP-Pad12)") (class "Default")
      (node (ref "U1") (pin "12") (pinfunction "COMPP_12") (pintype "unspecified"))
    )
    (net (code "43") (name "unconnected-(U1-FAULT#-Pad18)") (class "Default")
      (node (ref "U1") (pin "18") (pinfunction "FAULT#_18") (pintype "unspecified"))
    )
    (net (code "44") (name "unconnected-(U1-NC-Pad21)") (class "Default")
      (node (ref "U1") (pin "21") (pinfunction "NC_21") (pintype "unspecified"))
    )
    (net (code "45") (name "unconnected-(U2-COMPN-Pad13)") (class "Default")
      (node (ref "U2") (pin "13") (pinfunction "COMPN_13") (pintype "unspecified"))
    )
    (net (code "46") (name "unconnected-(U2-COMPO#-Pad19)") (class "Default")
      (node (ref "U2") (pin "19") (pinfunction "COMPO#_19") (pintype "unspecified"))
    )
    (net (code "47") (name "unconnected-(U2-COMPP-Pad12)") (class "Default")
      (node (ref "U2") (pin "12") (pinfunction "COMPP_12") (pintype "unspecified"))
    )
    (net (code "48") (name "unconnected-(U2-FAULT#-Pad18)") (class "Default")
      (node (ref "U2") (pin "18") (pinfunction "FAULT#_18") (pintype "unspecified"))
    )
    (net (code "49") (name "unconnected-(U2-NC-Pad21)") (class "Default")
      (node (ref "U2") (pin "21") (pinfunction "NC_21") (pintype "unspecified"))
    )
    (net (code "50") (name "unconnected-(U3-4Y-Pad11)") (class "Default")
      (node (ref "U3") (pin "11") (pinfunction "4Y_11") (pintype "unspecified"))
    )
  )
)
